# Non-relay_fused_CKT.net
KiCad netlist of a schematic drawn in Altium Designer
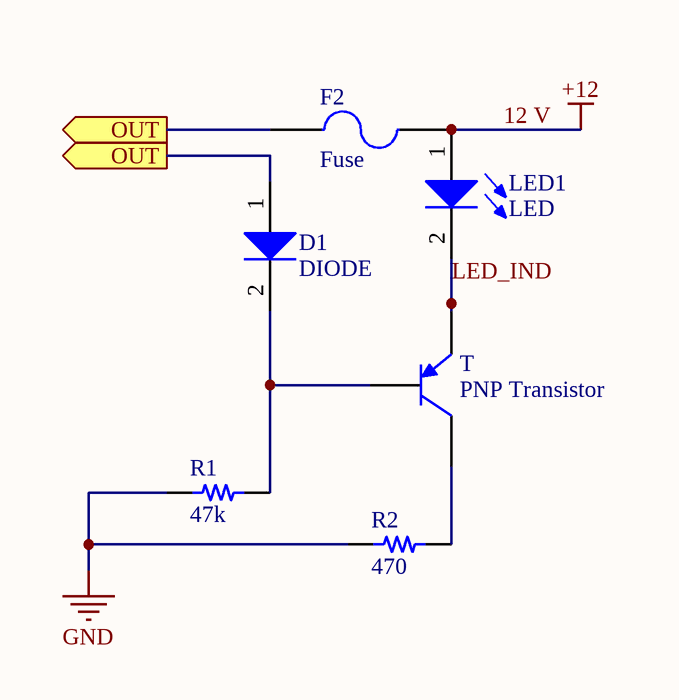
[diagram p0: Non-relay fused CKT.SchDoc]

(export (version "E")
  (design (tool "Eeschema 10.0.6"))
  (components
    (comp (ref "D1")
      (value "DIODE")
      (footprint "SOD123F")
      (description "Diode Super Barrier 40V 1A Surface Mount SOD-123F")
      (fields (field (name "POWER") "40V") (field (name "MFRPARTNO") "1N5819HW1-7-F"))
      (libsource (lib "Altium-Lib") (part "DIODE"))
    )
    (comp (ref "F2")
      (value "Fuse")
      (footprint "3568-MiniFuseHolder")
      (libsource (lib "Altium-Lib") (part "Fuse"))
    )
    (comp (ref "LED1") (value "LED") (footprint "0805_LED") (libsource (lib "Altium-Lib") (part "LED")))
    (comp (ref "R1")
      (value "47k")
      (footprint "RES 0805/2012")
      (fields
        (field (name "TOLERANCE") "1%")
        (field (name "POWER") "1/10W")
        (field (name "Comment") "Resistor 47k 0805 1/10W 1%")
        (field (name "CREATED_BY") "Nick Mah")
      )
      (libsource (lib "Altium-Lib") (part "Resistor"))
    )
    (comp (ref "R2")
      (value "470")
      (footprint "RES 0805/2012")
      (fields
        (field (name "TOLERANCE") "1%")
        (field (name "POWER") "1/10W")
        (field (name "Comment") "Resistor 470 0805 1/10W 1%")
        (field (name "CREATED_BY") "Nick Mah")
      )
      (libsource (lib "Altium-Lib") (part "Resistor"))
    )
    (comp (ref "T")
      (value "PNP Transistor")
      (footprint "SOT23-3")
      (fields (field (name "MFRPARTNO") "MMBT4403WT1G") (field (name "CREATED_BY") "Angel"))
      (libsource (lib "Altium-Lib") (part "PNP Transistor"))
    )
  )
  (nets
    (net (code "1") (name "+12") (class "Default")
      (node (ref "F2") (pin "2") (pinfunction "2_2") (pintype "passive"))
      (node (ref "LED1") (pin "1") (pinfunction "A_1") (pintype "passive"))
    )
    (net (code "2") (name "/LED_IND") (class "Default")
      (node (ref "LED1") (pin "2") (pinfunction "K_2") (pintype "passive"))
      (node (ref "T") (pin "2") (pinfunction "E_2") (pintype "passive"))
    )
    (net (code "3") (name "/OUT") (class "Default")
      (node (ref "D1") (pin "1") (pinfunction "A_1") (pintype "passive"))
      (node (ref "F2") (pin "1") (pinfunction "1_1") (pintype "passive"))
    )
    (net (code "4") (name "GND") (class "Default")
      (node (ref "R1") (pin "2") (pinfunction "2_2") (pintype "passive"))
      (node (ref "R2") (pin "2") (pinfunction "2_2") (pintype "passive"))
    )
    (net (code "5") (name "Net-(D1-K)") (class "Default")
      (node (ref "D1") (pin "2") (pinfunction "K_2") (pintype "passive"))
      (node (ref "R1") (pin "1") (pinfunction "1_1") (pintype "passive"))
      (node (ref "T") (pin "1") (pinfunction "B_1") (pintype "passive"))
    )
    (net (code "6") (name "Net-(T-C)") (class "Default")
      (node (ref "R2") (pin "1") (pinfunction "1_1") (pintype "passive"))
      (node (ref "T") (pin "3") (pinfunction "C_3") (pintype "passive"))
    )
  )
)
